# doodle_with_clock3_jump4.net
KiCad netlist of a schematic drawn in EAGLE
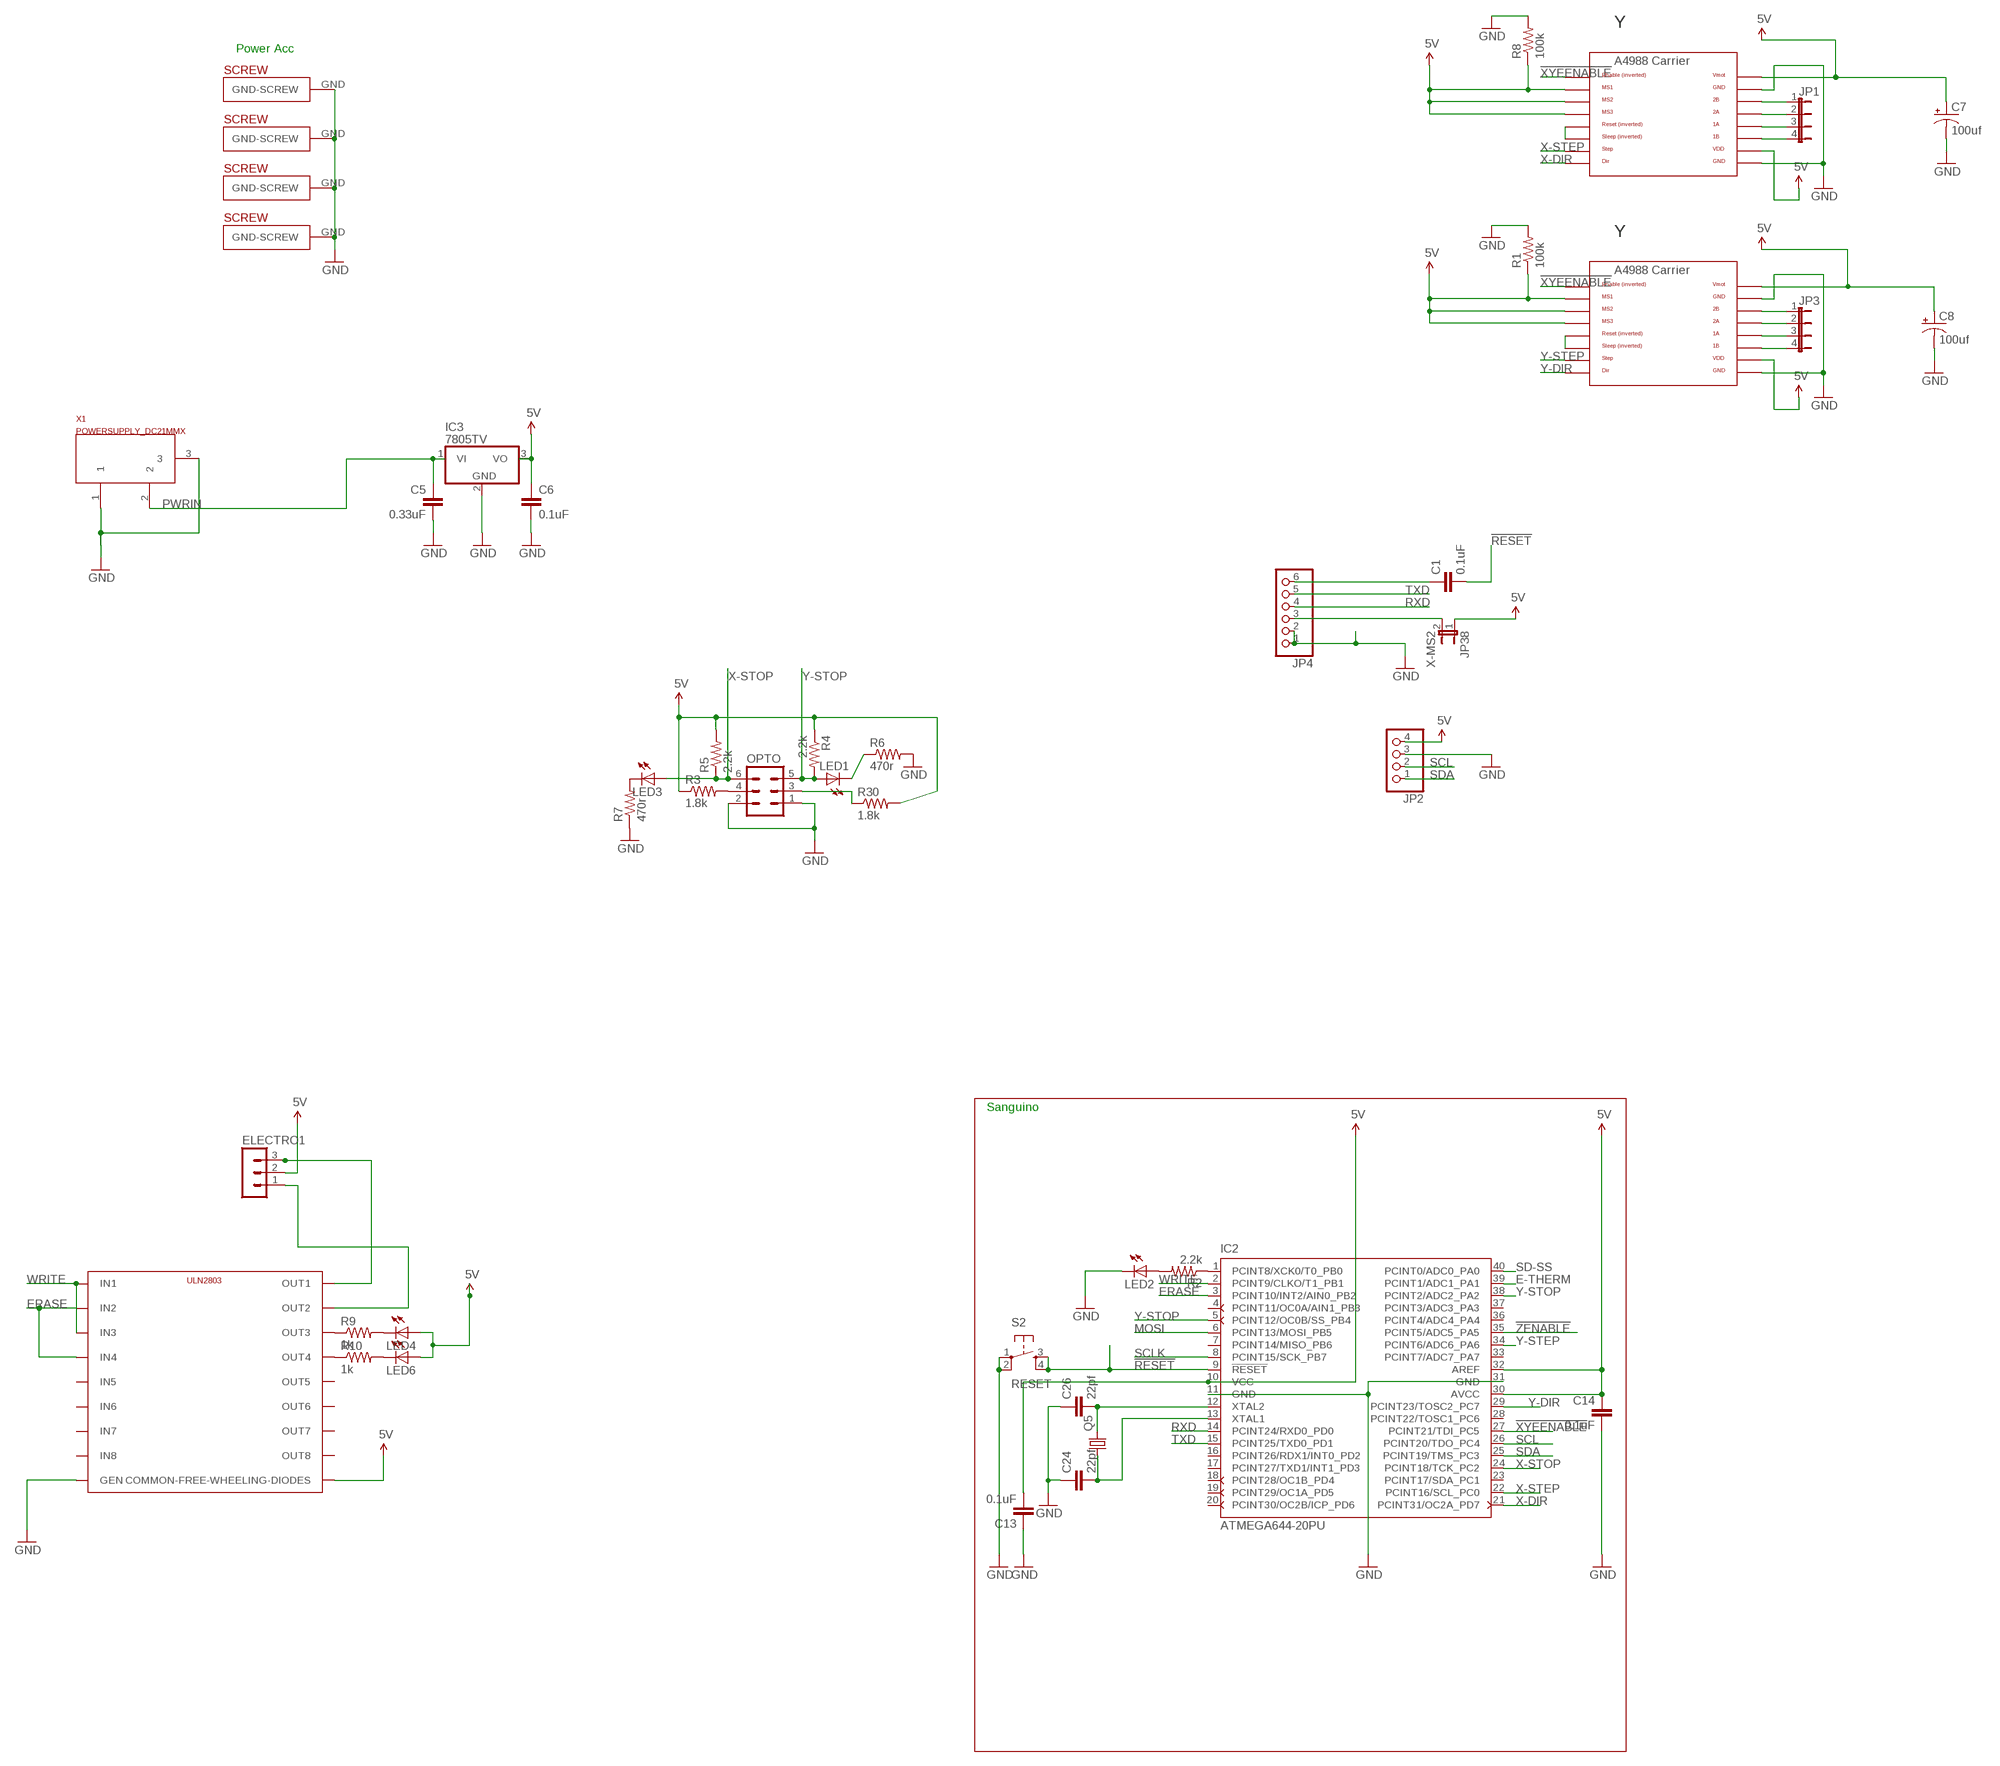
[diagram p0: schematic, sheet 1]

(export (version "E")
  (design (tool "Eeschema 10.0.6"))
  (components
    (comp (ref "C1")
      (value "0.1uF")
      (footprint "eagle-import:CAP-PTH-SMALL2")
      (libsource (lib "eagle-import") (part "CAPPTH2"))
    )
    (comp (ref "C5")
      (value "0.33uF")
      (footprint "eagle-import:CAP-PTH-SMALL2")
      (libsource (lib "eagle-import") (part "CAPPTH2"))
    )
    (comp (ref "C6")
      (value "0.1uF")
      (footprint "eagle-import:CAP-PTH-SMALL2")
      (libsource (lib "eagle-import") (part "CAPPTH2"))
    )
    (comp (ref "C7")
      (value "100uf")
      (footprint "eagle-import:CPOL-RADIAL-100UF-25V")
      (libsource (lib "eagle-import") (part "CAP_POLPTH1"))
    )
    (comp (ref "C8")
      (value "100uf")
      (footprint "eagle-import:CPOL-RADIAL-100UF-25V")
      (libsource (lib "eagle-import") (part "CAP_POLPTH1"))
    )
    (comp (ref "C13")
      (value "0.1uF")
      (footprint "eagle-import:CAP-PTH-SMALL2")
      (libsource (lib "eagle-import") (part "CAPPTH2"))
    )
    (comp (ref "C14")
      (value "0.1uF")
      (footprint "eagle-import:CAP-PTH-SMALL2")
      (libsource (lib "eagle-import") (part "CAPPTH2"))
    )
    (comp (ref "C24")
      (value "22pf")
      (footprint "eagle-import:CAP-PTH-SMALL2")
      (libsource (lib "eagle-import") (part "CAPPTH2"))
    )
    (comp (ref "C26")
      (value "22pf")
      (footprint "eagle-import:CAP-PTH-SMALL2")
      (libsource (lib "eagle-import") (part "CAPPTH2"))
    )
    (comp (ref "ELECTRO1")
      (value "MA03-1")
      (footprint "eagle-import:MA03-1")
      (libsource (lib "eagle-import") (part "MA03-1"))
    )
    (comp (ref "IC2")
      (value "ATMEGA644-20PU")
      (footprint "eagle-import:DIL40")
      (libsource (lib "eagle-import") (part "ATMEGA644-PU20"))
    )
    (comp (ref "IC3")
      (value "7805TV")
      (footprint "eagle-import:TO220V")
      (libsource (lib "eagle-import") (part "78TV05"))
    )
    (comp (ref "JP1")
      (value "JP4E")
      (footprint "eagle-import:JP4")
      (libsource (lib "eagle-import") (part "JP4E"))
    )
    (comp (ref "JP2")
      (value "PINHD-1X4")
      (footprint "eagle-import:1X04")
      (libsource (lib "eagle-import") (part "PINHD-1X4"))
    )
    (comp (ref "JP3")
      (value "JP4E")
      (footprint "eagle-import:JP4")
      (libsource (lib "eagle-import") (part "JP4E"))
    )
    (comp (ref "JP4")
      (value "PINHD-1X6/90")
      (footprint "eagle-import:1X06_90")
      (libsource (lib "eagle-import") (part "PINHD-1X6/90"))
    )
    (comp (ref "JP38")
      (value "X-MS2")
      (footprint "eagle-import:1X02")
      (libsource (lib "eagle-import") (part "JUMPER-2PTH"))
    )
    (comp (ref "LED1")
      (value "LED3MM")
      (footprint "eagle-import:LED3MM")
      (libsource (lib "eagle-import") (part "LED3MM"))
    )
    (comp (ref "LED2")
      (value "LED3MM")
      (footprint "eagle-import:LED3MM")
      (libsource (lib "eagle-import") (part "LED3MM"))
    )
    (comp (ref "LED3")
      (value "LED3MM")
      (footprint "eagle-import:LED3MM")
      (libsource (lib "eagle-import") (part "LED3MM"))
    )
    (comp (ref "LED4")
      (value "LED3MM")
      (footprint "eagle-import:LED3MM")
      (libsource (lib "eagle-import") (part "LED3MM"))
    )
    (comp (ref "LED6")
      (value "LED3MM")
      (footprint "eagle-import:LED3MM")
      (libsource (lib "eagle-import") (part "LED3MM"))
    )
    (comp (ref "OPTO")
      (value "MA03-2")
      (footprint "eagle-import:MA03-2")
      (libsource (lib "eagle-import") (part "MA03-2"))
    )
    (comp (ref "Q5")
      (value "CRYSTALHC49S")
      (footprint "eagle-import:HC49_S")
      (libsource (lib "eagle-import") (part "CRYSTALHC49S"))
    )
    (comp (ref "R1")
      (value "100k")
      (footprint "eagle-import:0207_7")
      (libsource (lib "eagle-import") (part "R-US_0207/7"))
    )
    (comp (ref "R2")
      (value "2.2k")
      (footprint "eagle-import:0207_2V")
      (libsource (lib "eagle-import") (part "resistor_R-US_0207/2V"))
    )
    (comp (ref "R3")
      (value "1.8k")
      (footprint "eagle-import:0207_2V")
      (libsource (lib "eagle-import") (part "resistor_R-US_0207/2V"))
    )
    (comp (ref "R4")
      (value "2.2k")
      (footprint "eagle-import:0207_2V")
      (libsource (lib "eagle-import") (part "resistor_R-US_0207/2V"))
    )
    (comp (ref "R5")
      (value "2.2k")
      (footprint "eagle-import:0207_2V")
      (libsource (lib "eagle-import") (part "resistor_R-US_0207/2V"))
    )
    (comp (ref "R6")
      (value "470r")
      (footprint "eagle-import:0207_2V")
      (libsource (lib "eagle-import") (part "resistor_R-US_0207/2V"))
    )
    (comp (ref "R7")
      (value "470r")
      (footprint "eagle-import:0207_2V")
      (libsource (lib "eagle-import") (part "resistor_R-US_0207/2V"))
    )
    (comp (ref "R8")
      (value "100k")
      (footprint "eagle-import:0207_7")
      (libsource (lib "eagle-import") (part "R-US_0207/7"))
    )
    (comp (ref "R9")
      (value "1k")
      (footprint "eagle-import:0207_2V")
      (libsource (lib "eagle-import") (part "resistor_R-US_0207/2V"))
    )
    (comp (ref "R10")
      (value "1k")
      (footprint "eagle-import:0207_2V")
      (libsource (lib "eagle-import") (part "resistor_R-US_0207/2V"))
    )
    (comp (ref "R30")
      (value "1.8k")
      (footprint "eagle-import:0207_2V")
      (libsource (lib "eagle-import") (part "resistor_R-US_0207/2V"))
    )
    (comp (ref "S2")
      (value "RESET")
      (footprint "eagle-import:TACTILE-PTH")
      (libsource (lib "eagle-import") (part "TAC_SWITCHPTH"))
    )
    (comp (ref "U$1")
      (value "A4988BREAKOUT")
      (footprint "eagle-import:A4988BREAKOUT")
      (libsource (lib "eagle-import") (part "A4988BREAKOUT"))
    )
    (comp (ref "U$2")
      (value "ULN2803")
      (footprint "eagle-import:P-DIP")
      (libsource (lib "eagle-import") (part "ULN2803"))
    )
    (comp (ref "U$7")
      (value "A4988BREAKOUT")
      (footprint "eagle-import:A4988BREAKOUT")
      (libsource (lib "eagle-import") (part "A4988BREAKOUT"))
    )
    (comp (ref "U$14")
      (value "PLATED-SCREW")
      (footprint "eagle-import:PLATEDSCREW")
      (libsource (lib "eagle-import") (part "PLATED-SCREW"))
    )
    (comp (ref "U$17")
      (value "PLATED-SCREW")
      (footprint "eagle-import:PLATEDSCREW")
      (libsource (lib "eagle-import") (part "PLATED-SCREW"))
    )
    (comp (ref "U$18")
      (value "PLATED-SCREW")
      (footprint "eagle-import:PLATEDSCREW")
      (libsource (lib "eagle-import") (part "PLATED-SCREW"))
    )
    (comp (ref "U$38")
      (value "PLATED-SCREW")
      (footprint "eagle-import:PLATEDSCREW")
      (libsource (lib "eagle-import") (part "PLATED-SCREW"))
    )
    (comp (ref "X1")
      (value "POWERSUPPLY_DC21MMX")
      (footprint "eagle-import:POWERSUPPLY_DC-21MM")
      (libsource (lib "eagle-import") (part "POWERSUPPLY_DC21MMX"))
    )
  )
  (nets
    (net (code "1") (name "/E-THERM") (class "Default")
      (node (ref "IC2") (pin "39") (pinfunction "PCINT1/ADC1_PA1_39") (pintype "bidirectional"))
    )
    (net (code "2") (name "/ERASE") (class "Default")
      (node (ref "IC2") (pin "3") (pinfunction "PCINT10/INT2/AIN0_PB2_3") (pintype "bidirectional"))
      (node (ref "U$2") (pin "IN2") (pinfunction "IN2_IN2") (pintype "input"))
      (node (ref "U$2") (pin "IN4") (pinfunction "IN4_IN4") (pintype "input"))
    )
    (net (code "3") (name "/MOSI") (class "Default")
      (node (ref "IC2") (pin "6") (pinfunction "PCINT13/MOSI_PB5_6") (pintype "bidirectional"))
    )
    (net (code "4") (name "/PWRIN") (class "Default")
      (node (ref "C5") (pin "1") (pinfunction "1_1") (pintype "passive"))
      (node (ref "IC3") (pin "1") (pinfunction "VI_1") (pintype "input"))
      (node (ref "X1") (pin "2") (pinfunction "2_2") (pintype "power_in"))
    )
    (net (code "5") (name "/RXD") (class "Default")
      (node (ref "IC2") (pin "14") (pinfunction "PCINT24/RXD0_PD0_14") (pintype "bidirectional"))
      (node (ref "JP4") (pin "4") (pinfunction "4_4") (pintype "passive"))
    )
    (net (code "6") (name "/SCL") (class "Default")
      (node (ref "IC2") (pin "26") (pinfunction "PCINT20/TDO_PC4_26") (pintype "bidirectional"))
      (node (ref "JP2") (pin "2") (pinfunction "2_2") (pintype "passive"))
    )
    (net (code "7") (name "/SCLK") (class "Default")
      (node (ref "IC2") (pin "8") (pinfunction "PCINT15/SCK_PB7_8") (pintype "bidirectional"))
    )
    (net (code "8") (name "/SD-SS") (class "Default")
      (node (ref "IC2") (pin "40") (pinfunction "PCINT0/ADC0_PA0_40") (pintype "bidirectional"))
    )
    (net (code "9") (name "/SDA") (class "Default")
      (node (ref "IC2") (pin "25") (pinfunction "PCINT19/TMS_PC3_25") (pintype "bidirectional"))
      (node (ref "JP2") (pin "1") (pinfunction "1_1") (pintype "passive"))
    )
    (net (code "10") (name "/TXD") (class "Default")
      (node (ref "IC2") (pin "15") (pinfunction "PCINT25/TXD0_PD1_15") (pintype "bidirectional"))
      (node (ref "JP4") (pin "5") (pinfunction "5_5") (pintype "passive"))
    )
    (net (code "11") (name "/WRITE") (class "Default")
      (node (ref "IC2") (pin "2") (pinfunction "PCINT9/CLKO/T1_PB1_2") (pintype "bidirectional"))
      (node (ref "U$2") (pin "IN1") (pinfunction "IN1_IN1") (pintype "input"))
      (node (ref "U$2") (pin "IN3") (pinfunction "IN3_IN3") (pintype "input"))
    )
    (net (code "12") (name "/X-DIR") (class "Default")
      (node (ref "IC2") (pin "21") (pinfunction "PCINT31/OC2A_PD7_21") (pintype "bidirectional"))
      (node (ref "U$7") (pin "DIR") (pinfunction "DIR_DIR") (pintype "input"))
    )
    (net (code "13") (name "/X-STEP") (class "Default")
      (node (ref "IC2") (pin "22") (pinfunction "PCINT16/SCL_PC0_22") (pintype "bidirectional"))
      (node (ref "U$7") (pin "STEP") (pinfunction "STEP_STEP") (pintype "input"))
    )
    (net (code "14") (name "/X-STOP") (class "Default")
      (node (ref "IC2") (pin "24") (pinfunction "PCINT18/TCK_PC2_24") (pintype "bidirectional"))
      (node (ref "LED3") (pin "A") (pinfunction "A_A") (pintype "passive"))
      (node (ref "OPTO") (pin "6") (pinfunction "6_6") (pintype "passive"))
      (node (ref "R5") (pin "1") (pinfunction "1_1") (pintype "passive"))
    )
    (net (code "15") (name "/Y-DIR") (class "Default")
      (node (ref "IC2") (pin "29") (pinfunction "PCINT23/TOSC2_PC7_29") (pintype "bidirectional"))
      (node (ref "U$1") (pin "DIR") (pinfunction "DIR_DIR") (pintype "input"))
    )
    (net (code "16") (name "/Y-STEP") (class "Default")
      (node (ref "IC2") (pin "34") (pinfunction "PCINT6/ADC6_PA6_34") (pintype "bidirectional"))
      (node (ref "U$1") (pin "STEP") (pinfunction "STEP_STEP") (pintype "input"))
    )
    (net (code "17") (name "/Y-STOP") (class "Default")
      (node (ref "IC2") (pin "38") (pinfunction "PCINT2/ADC2_PA2_38") (pintype "bidirectional"))
      (node (ref "IC2") (pin "5") (pinfunction "PCINT12/OC0B/SS_PB4_5") (pintype "bidirectional"))
      (node (ref "LED1") (pin "A") (pinfunction "A_A") (pintype "passive"))
      (node (ref "OPTO") (pin "5") (pinfunction "5_5") (pintype "passive"))
      (node (ref "R4") (pin "2") (pinfunction "2_2") (pintype "passive"))
    )
    (net (code "18") (name "/~{RESET}") (class "Default")
      (node (ref "C1") (pin "2") (pinfunction "2_2") (pintype "passive"))
      (node (ref "IC2") (pin "9") (pinfunction "~{RESET}_9") (pintype "input"))
      (node (ref "S2") (pin "3") (pinfunction "3_3") (pintype "passive"))
      (node (ref "S2") (pin "4") (pinfunction "4_4") (pintype "passive"))
    )
    (net (code "19") (name "/~{XYEENABLE}") (class "Default")
      (node (ref "IC2") (pin "27") (pinfunction "PCINT21/TDI_PC5_27") (pintype "bidirectional"))
      (node (ref "U$1") (pin "EN") (pinfunction "EN_EN") (pintype "input"))
      (node (ref "U$7") (pin "EN") (pinfunction "EN_EN") (pintype "input"))
    )
    (net (code "20") (name "/~{ZENABLE}") (class "Default")
      (node (ref "IC2") (pin "35") (pinfunction "PCINT5/ADC5_PA5_35") (pintype "bidirectional"))
    )
    (net (code "21") (name "5V") (class "Default")
      (node (ref "C13") (pin "2") (pinfunction "2_2") (pintype "passive"))
      (node (ref "C14") (pin "1") (pinfunction "1_1") (pintype "passive"))
      (node (ref "C6") (pin "1") (pinfunction "1_1") (pintype "passive"))
      (node (ref "C7") (pin "1") (pinfunction "+_1") (pintype "passive"))
      (node (ref "C8") (pin "1") (pinfunction "+_1") (pintype "passive"))
      (node (ref "ELECTRO1") (pin "2") (pinfunction "2_2") (pintype "passive"))
      (node (ref "IC2") (pin "10") (pinfunction "VCC_10") (pintype "power_in"))
      (node (ref "IC2") (pin "30") (pinfunction "AVCC_30") (pintype "power_in"))
      (node (ref "IC2") (pin "32") (pinfunction "AREF_32") (pintype "passive"))
      (node (ref "IC3") (pin "3") (pinfunction "VO_3") (pintype "passive"))
      (node (ref "JP2") (pin "4") (pinfunction "4_4") (pintype "passive"))
      (node (ref "JP38") (pin "1") (pinfunction "1_1") (pintype "passive"))
      (node (ref "LED4") (pin "A") (pinfunction "A_A") (pintype "passive"))
      (node (ref "LED6") (pin "A") (pinfunction "A_A") (pintype "passive"))
      (node (ref "R1") (pin "1") (pinfunction "1_1") (pintype "passive"))
      (node (ref "R3") (pin "1") (pinfunction "1_1") (pintype "passive"))
      (node (ref "R30") (pin "2") (pinfunction "2_2") (pintype "passive"))
      (node (ref "R4") (pin "1") (pinfunction "1_1") (pintype "passive"))
      (node (ref "R5") (pin "2") (pinfunction "2_2") (pintype "passive"))
      (node (ref "R8") (pin "1") (pinfunction "1_1") (pintype "passive"))
      (node (ref "U$1") (pin "MS1") (pinfunction "MS1_MS1") (pintype "input"))
      (node (ref "U$1") (pin "MS2") (pinfunction "MS2_MS2") (pintype "input"))
      (node (ref "U$1") (pin "MS3") (pinfunction "MS3_MS3") (pintype "input"))
      (node (ref "U$1") (pin "VDD") (pinfunction "VDD_VDD") (pintype "power_in"))
      (node (ref "U$1") (pin "VMOT") (pinfunction "VMOT_VMOT") (pintype "power_in"))
      (node (ref "U$2") (pin "COMMON-FREE-WHEELING-DIODES") (pinfunction "COMMON-FREE-WHEELING-DIODES_COMMON-FREE-WHEELING-DIODES") (pintype "output"))
      (node (ref "U$7") (pin "MS1") (pinfunction "MS1_MS1") (pintype "input"))
      (node (ref "U$7") (pin "MS2") (pinfunction "MS2_MS2") (pintype "input"))
      (node (ref "U$7") (pin "MS3") (pinfunction "MS3_MS3") (pintype "input"))
      (node (ref "U$7") (pin "VDD") (pinfunction "VDD_VDD") (pintype "power_in"))
      (node (ref "U$7") (pin "VMOT") (pinfunction "VMOT_VMOT") (pintype "power_in"))
    )
    (net (code "22") (name "GND") (class "Default")
      (node (ref "C13") (pin "1") (pinfunction "1_1") (pintype "passive"))
      (node (ref "C14") (pin "2") (pinfunction "2_2") (pintype "passive"))
      (node (ref "C24") (pin "1") (pinfunction "1_1") (pintype "passive"))
      (node (ref "C26") (pin "1") (pinfunction "1_1") (pintype "passive"))
      (node (ref "C5") (pin "2") (pinfunction "2_2") (pintype "passive"))
      (node (ref "C6") (pin "2") (pinfunction "2_2") (pintype "passive"))
      (node (ref "C7") (pin "2") (pinfunction "-_2") (pintype "passive"))
      (node (ref "C8") (pin "2") (pinfunction "-_2") (pintype "passive"))
      (node (ref "IC2") (pin "11") (pinfunction "GND_11") (pintype "power_in"))
      (node (ref "IC2") (pin "31") (pinfunction "GND_31") (pintype "power_in"))
      (node (ref "IC3") (pin "2") (pinfunction "GND_2") (pintype "passive"))
      (node (ref "JP2") (pin "3") (pinfunction "3_3") (pintype "passive"))
      (node (ref "JP4") (pin "1") (pinfunction "1_1") (pintype "passive"))
      (node (ref "JP4") (pin "2") (pinfunction "2_2") (pintype "passive"))
      (node (ref "LED2") (pin "K") (pinfunction "C_K") (pintype "passive"))
      (node (ref "OPTO") (pin "1") (pinfunction "1_1") (pintype "passive"))
      (node (ref "OPTO") (pin "2") (pinfunction "2_2") (pintype "passive"))
      (node (ref "R1") (pin "2") (pinfunction "2_2") (pintype "passive"))
      (node (ref "R6") (pin "2") (pinfunction "2_2") (pintype "passive"))
      (node (ref "R7") (pin "1") (pinfunction "1_1") (pintype "passive"))
      (node (ref "R8") (pin "2") (pinfunction "2_2") (pintype "passive"))
      (node (ref "S2") (pin "1") (pinfunction "1_1") (pintype "passive"))
      (node (ref "S2") (pin "2") (pinfunction "2_2") (pintype "passive"))
      (node (ref "U$1") (pin "GND") (pinfunction "GND_GND") (pintype "power_in"))
      (node (ref "U$1") (pin "GND@0") (pinfunction "GND_GND@0") (pintype "power_in"))
      (node (ref "U$14") (pin "GND") (pinfunction "GND-SCREW_GND") (pintype "bidirectional"))
      (node (ref "U$17") (pin "GND") (pinfunction "GND-SCREW_GND") (pintype "bidirectional"))
      (node (ref "U$18") (pin "GND") (pinfunction "GND-SCREW_GND") (pintype "bidirectional"))
      (node (ref "U$2") (pin "GEN") (pinfunction "GEN_GEN") (pintype "power_in"))
      (node (ref "U$38") (pin "GND") (pinfunction "GND-SCREW_GND") (pintype "bidirectional"))
      (node (ref "U$7") (pin "GND") (pinfunction "GND_GND") (pintype "power_in"))
      (node (ref "U$7") (pin "GND@0") (pinfunction "GND_GND@0") (pintype "power_in"))
      (node (ref "X1") (pin "1") (pinfunction "1_1") (pintype "power_in"))
      (node (ref "X1") (pin "3") (pinfunction "3_3") (pintype "power_in"))
    )
    (net (code "23") (name "Net-(C1-Pad1)") (class "Default")
      (node (ref "C1") (pin "1") (pinfunction "1_1") (pintype "passive"))
      (node (ref "JP4") (pin "6") (pinfunction "6_6") (pintype "passive"))
    )
    (net (code "24") (name "Net-(ELECTRO1-Pad1)") (class "Default")
      (node (ref "ELECTRO1") (pin "1") (pinfunction "1_1") (pintype "passive"))
      (node (ref "U$2") (pin "OUT2") (pinfunction "OUT2_OUT2") (pintype "output"))
    )
    (net (code "25") (name "Net-(ELECTRO1-Pad3)") (class "Default")
      (node (ref "ELECTRO1") (pin "3") (pinfunction "3_3") (pintype "passive"))
      (node (ref "U$2") (pin "OUT1") (pinfunction "OUT1_OUT1") (pintype "output"))
    )
    (net (code "26") (name "Net-(IC2-PCINT8{slash}XCK0{slash}T0_PB0)") (class "Default")
      (node (ref "IC2") (pin "1") (pinfunction "PCINT8/XCK0/T0_PB0_1") (pintype "bidirectional"))
      (node (ref "R2") (pin "1") (pinfunction "1_1") (pintype "passive"))
    )
    (net (code "27") (name "Net-(IC2-XTAL1)") (class "Default")
      (node (ref "C24") (pin "2") (pinfunction "2_2") (pintype "passive"))
      (node (ref "IC2") (pin "13") (pinfunction "XTAL1_13") (pintype "input"))
      (node (ref "Q5") (pin "1") (pinfunction "1_1") (pintype "passive"))
    )
    (net (code "28") (name "Net-(IC2-XTAL2)") (class "Default")
      (node (ref "C26") (pin "2") (pinfunction "2_2") (pintype "passive"))
      (node (ref "IC2") (pin "12") (pinfunction "XTAL2_12") (pintype "output"))
      (node (ref "Q5") (pin "2") (pinfunction "2_2") (pintype "passive"))
    )
    (net (code "29") (name "Net-(JP1-Pad1)") (class "Default")
      (node (ref "JP1") (pin "1") (pinfunction "1_1") (pintype "passive"))
      (node (ref "U$7") (pin "2B") (pinfunction "2B_2B") (pintype "output"))
    )
    (net (code "30") (name "Net-(JP1-Pad2)") (class "Default")
      (node (ref "JP1") (pin "2") (pinfunction "2_2") (pintype "passive"))
      (node (ref "U$7") (pin "2A") (pinfunction "2A_2A") (pintype "output"))
    )
    (net (code "31") (name "Net-(JP1-Pad3)") (class "Default")
      (node (ref "JP1") (pin "3") (pinfunction "3_3") (pintype "passive"))
      (node (ref "U$7") (pin "1A") (pinfunction "1A_1A") (pintype "output"))
    )
    (net (code "32") (name "Net-(JP1-Pad4)") (class "Default")
      (node (ref "JP1") (pin "4") (pinfunction "4_4") (pintype "passive"))
      (node (ref "U$7") (pin "1B") (pinfunction "1B_1B") (pintype "output"))
    )
    (net (code "33") (name "Net-(JP3-Pad1)") (class "Default")
      (node (ref "JP3") (pin "1") (pinfunction "1_1") (pintype "passive"))
      (node (ref "U$1") (pin "2B") (pinfunction "2B_2B") (pintype "output"))
    )
    (net (code "34") (name "Net-(JP3-Pad2)") (class "Default")
      (node (ref "JP3") (pin "2") (pinfunction "2_2") (pintype "passive"))
      (node (ref "U$1") (pin "2A") (pinfunction "2A_2A") (pintype "output"))
    )
    (net (code "35") (name "Net-(JP3-Pad3)") (class "Default")
      (node (ref "JP3") (pin "3") (pinfunction "3_3") (pintype "passive"))
      (node (ref "U$1") (pin "1A") (pinfunction "1A_1A") (pintype "output"))
    )
    (net (code "36") (name "Net-(JP3-Pad4)") (class "Default")
      (node (ref "JP3") (pin "4") (pinfunction "4_4") (pintype "passive"))
      (node (ref "U$1") (pin "1B") (pinfunction "1B_1B") (pintype "output"))
    )
    (net (code "37") (name "Net-(JP38-Pad2)") (class "Default")
      (node (ref "JP38") (pin "2") (pinfunction "2_2") (pintype "passive"))
      (node (ref "JP4") (pin "3") (pinfunction "3_3") (pintype "passive"))
    )
    (net (code "38") (name "Net-(LED1-C)") (class "Default")
      (node (ref "LED1") (pin "K") (pinfunction "C_K") (pintype "passive"))
      (node (ref "R6") (pin "1") (pinfunction "1_1") (pintype "passive"))
    )
    (net (code "39") (name "Net-(LED2-PadA)") (class "Default")
      (node (ref "LED2") (pin "A") (pinfunction "A_A") (pintype "passive"))
      (node (ref "R2") (pin "2") (pinfunction "2_2") (pintype "passive"))
    )
    (net (code "40") (name "Net-(LED3-C)") (class "Default")
      (node (ref "LED3") (pin "K") (pinfunction "C_K") (pintype "passive"))
      (node (ref "R7") (pin "2") (pinfunction "2_2") (pintype "passive"))
    )
    (net (code "41") (name "Net-(LED4-C)") (class "Default")
      (node (ref "LED4") (pin "K") (pinfunction "C_K") (pintype "passive"))
      (node (ref "R9") (pin "2") (pinfunction "2_2") (pintype "passive"))
    )
    (net (code "42") (name "Net-(LED6-C)") (class "Default")
      (node (ref "LED6") (pin "K") (pinfunction "C_K") (pintype "passive"))
      (node (ref "R10") (pin "2") (pinfunction "2_2") (pintype "passive"))
    )
    (net (code "43") (name "Net-(OPTO-Pad3)") (class "Default")
      (node (ref "OPTO") (pin "3") (pinfunction "3_3") (pintype "passive"))
      (node (ref "R30") (pin "1") (pinfunction "1_1") (pintype "passive"))
    )
    (net (code "44") (name "Net-(OPTO-Pad4)") (class "Default")
      (node (ref "OPTO") (pin "4") (pinfunction "4_4") (pintype "passive"))
      (node (ref "R3") (pin "2") (pinfunction "2_2") (pintype "passive"))
    )
    (net (code "45") (name "Net-(R9-Pad1)") (class "Default")
      (node (ref "R9") (pin "1") (pinfunction "1_1") (pintype "passive"))
      (node (ref "U$2") (pin "OUT3") (pinfunction "OUT3_OUT3") (pintype "output"))
    )
    (net (code "46") (name "Net-(R10-Pad1)") (class "Default")
      (node (ref "R10") (pin "1") (pinfunction "1_1") (pintype "passive"))
      (node (ref "U$2") (pin "OUT4") (pinfunction "OUT4_OUT4") (pintype "output"))
    )
    (net (code "47") (name "Net-(U$1-SLEEP)") (class "Default")
      (node (ref "U$1") (pin "RST") (pinfunction "RST_RST") (pintype "input"))
      (node (ref "U$1") (pin "SLP") (pinfunction "SLEEP_SLP") (pintype "input"))
    )
    (net (code "48") (name "Net-(U$7-SLEEP)") (class "Default")
      (node (ref "U$7") (pin "RST") (pinfunction "RST_RST") (pintype "input"))
      (node (ref "U$7") (pin "SLP") (pinfunction "SLEEP_SLP") (pintype "input"))
    )
    (net (code "49") (name "unconnected-(IC2-PCINT3{slash}ADC3_PA3-Pad37)") (class "Default")
      (node (ref "IC2") (pin "37") (pinfunction "PCINT3/ADC3_PA3_37") (pintype "bidirectional"))
    )
    (net (code "50") (name "unconnected-(IC2-PCINT4{slash}ADC4_PA4-Pad36)") (class "Default")
      (node (ref "IC2") (pin "36") (pinfunction "PCINT4/ADC4_PA4_36") (pintype "bidirectional"))
    )
    (net (code "51") (name "unconnected-(IC2-PCINT7{slash}ADC7_PA7-Pad33)") (class "Default")
      (node (ref "IC2") (pin "33") (pinfunction "PCINT7/ADC7_PA7_33") (pintype "bidirectional"))
    )
    (net (code "52") (name "unconnected-(IC2-PCINT11{slash}OC0A{slash}AIN1_PB3-Pad4)") (class "Default")
      (node (ref "IC2") (pin "4") (pinfunction "PCINT11/OC0A/AIN1_PB3_4") (pintype "bidirectional"))
    )
    (net (code "53") (name "unconnected-(IC2-PCINT14{slash}MISO_PB6-Pad7)") (class "Default")
      (node (ref "IC2") (pin "7") (pinfunction "PCINT14/MISO_PB6_7") (pintype "bidirectional"))
    )
    (net (code "54") (name "unconnected-(IC2-PCINT17{slash}SDA_PC1-Pad23)") (class "Default")
      (node (ref "IC2") (pin "23") (pinfunction "PCINT17/SDA_PC1_23") (pintype "bidirectional"))
    )
    (net (code "55") (name "unconnected-(IC2-PCINT22{slash}TOSC1_PC6-Pad28)") (class "Default")
      (node (ref "IC2") (pin "28") (pinfunction "PCINT22/TOSC1_PC6_28") (pintype "bidirectional"))
    )
    (net (code "56") (name "unconnected-(IC2-PCINT26{slash}RDX1{slash}INT0_PD2-Pad16)") (class "Default")
      (node (ref "IC2") (pin "16") (pinfunction "PCINT26/RDX1/INT0_PD2_16") (pintype "bidirectional"))
    )
    (net (code "57") (name "unconnected-(IC2-PCINT27{slash}TXD1{slash}INT1_PD3-Pad17)") (class "Default")
      (node (ref "IC2") (pin "17") (pinfunction "PCINT27/TXD1/INT1_PD3_17") (pintype "bidirectional"))
    )
    (net (code "58") (name "unconnected-(IC2-PCINT28{slash}OC1B_PD4-Pad18)") (class "Default")
      (node (ref "IC2") (pin "18") (pinfunction "PCINT28/OC1B_PD4_18") (pintype "bidirectional"))
    )
    (net (code "59") (name "unconnected-(IC2-PCINT29{slash}OC1A_PD5-Pad19)") (class "Default")
      (node (ref "IC2") (pin "19") (pinfunction "PCINT29/OC1A_PD5_19") (pintype "bidirectional"))
    )
    (net (code "60") (name "unconnected-(IC2-PCINT30{slash}OC2B{slash}ICP_PD6-Pad20)") (class "Default")
      (node (ref "IC2") (pin "20") (pinfunction "PCINT30/OC2B/ICP_PD6_20") (pintype "bidirectional"))
    )
    (net (code "61") (name "unconnected-(U$2-PadIN5)") (class "Default")
      (node (ref "U$2") (pin "IN5") (pinfunction "IN5_IN5") (pintype "input"))
    )
    (net (code "62") (name "unconnected-(U$2-PadIN6)") (class "Default")
      (node (ref "U$2") (pin "IN6") (pinfunction "IN6_IN6") (pintype "input"))
    )
    (net (code "63") (name "unconnected-(U$2-PadIN7)") (class "Default")
      (node (ref "U$2") (pin "IN7") (pinfunction "IN7_IN7") (pintype "input"))
    )
    (net (code "64") (name "unconnected-(U$2-PadIN8)") (class "Default")
      (node (ref "U$2") (pin "IN8") (pinfunction "IN8_IN8") (pintype "input"))
    )
    (net (code "65") (name "unconnected-(U$2-PadOUT5)") (class "Default")
      (node (ref "U$2") (pin "OUT5") (pinfunction "OUT5_OUT5") (pintype "output"))
    )
    (net (code "66") (name "unconnected-(U$2-PadOUT6)") (class "Default")
      (node (ref "U$2") (pin "OUT6") (pinfunction "OUT6_OUT6") (pintype "output"))
    )
    (net (code "67") (name "unconnected-(U$2-PadOUT7)") (class "Default")
      (node (ref "U$2") (pin "OUT7") (pinfunction "OUT7_OUT7") (pintype "output"))
    )
    (net (code "68") (name "unconnected-(U$2-PadOUT8)") (class "Default")
      (node (ref "U$2") (pin "OUT8") (pinfunction "OUT8_OUT8") (pintype "output"))
    )
  )
)
